# Apo_Board_2017_ATmega328_SMD.net
KiCad netlist of a schematic drawn in EAGLE
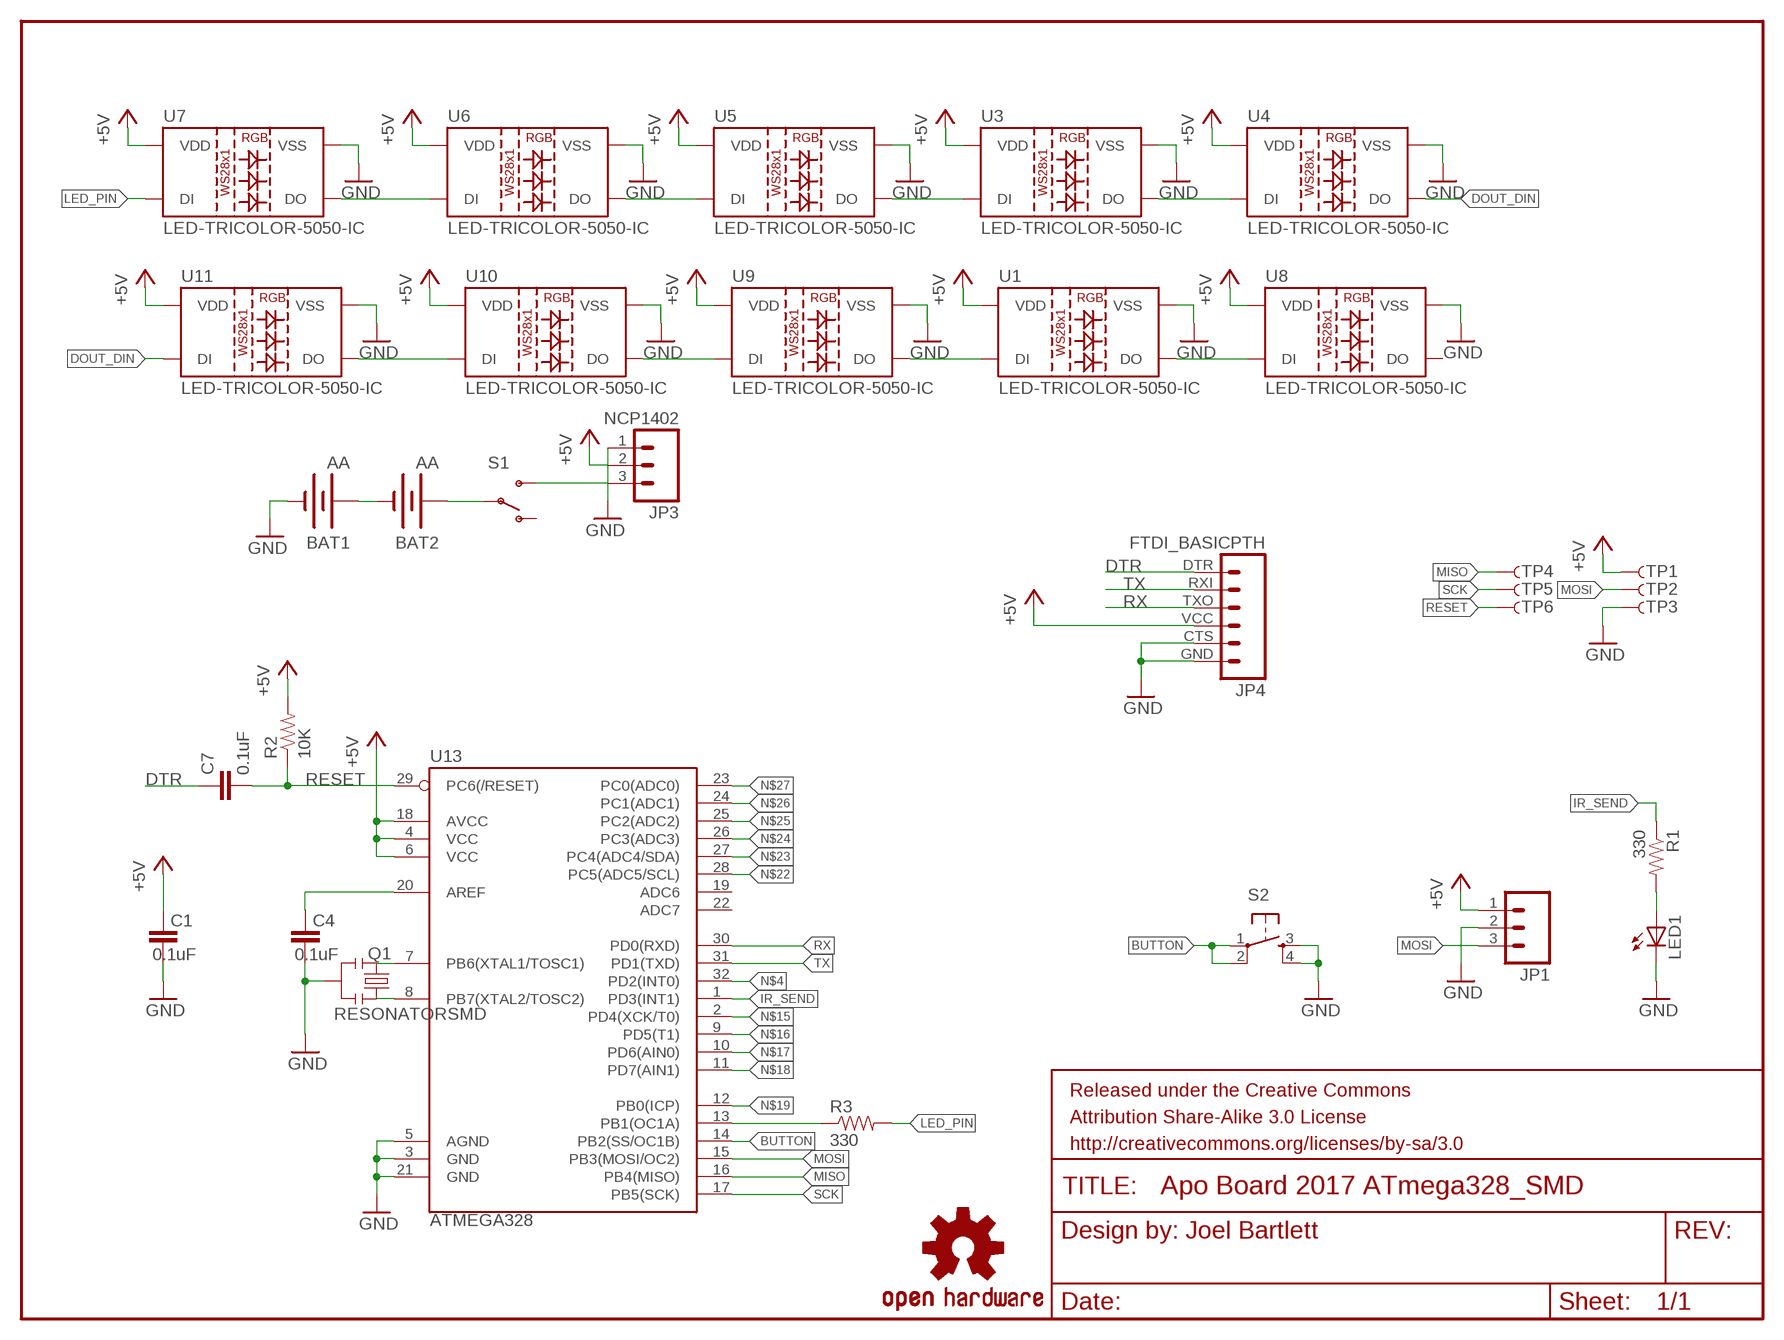
[diagram p0: schematic, sheet 1]

(export (version "E")
  (design (tool "Eeschema 10.0.6"))
  (components
    (comp (ref "BAT1")
      (value "AA")
      (footprint "eagle-import:BATTERY-AA-KIT")
      (libsource (lib "eagle-import") (part "BATTERYAA-KIT"))
    )
    (comp (ref "BAT2")
      (value "AA")
      (footprint "eagle-import:BATTERY-AA-KIT")
      (libsource (lib "eagle-import") (part "BATTERYAA-KIT"))
    )
    (comp (ref "C1")
      (value "0.1uF")
      (footprint "eagle-import:0402-CAP")
      (libsource (lib "eagle-import") (part "CAP0402-CAP"))
    )
    (comp (ref "C4")
      (value "0.1uF")
      (footprint "eagle-import:0402-CAP")
      (libsource (lib "eagle-import") (part "CAP0402-CAP"))
    )
    (comp (ref "C7")
      (value "0.1uF")
      (footprint "eagle-import:0402-CAP")
      (libsource (lib "eagle-import") (part "CAP0402-CAP"))
    )
    (comp (ref "FRAME1")
      (value "FRAME-LETTER")
      (footprint "eagle-import:CREATIVE_COMMONS")
      (libsource (lib "eagle-import") (part "FRAME-LETTER"))
    )
    (comp (ref "JP1")
      (value "M03IR_RECEIVER")
      (footprint "eagle-import:1X03_IR_RECEIVER")
      (libsource (lib "eagle-import") (part "M03IR_RECEIVER"))
    )
    (comp (ref "JP3")
      (value "NCP1402")
      (footprint "eagle-import:1X03_BOOST")
      (libsource (lib "eagle-import") (part "M03BOOST"))
    )
    (comp (ref "JP4")
      (value "FTDI_BASICPTH")
      (footprint "eagle-import:FTDI_BASIC")
      (libsource (lib "eagle-import") (part "FTDI_BASICPTH"))
    )
    (comp (ref "LED1")
      (value "LED5MM")
      (footprint "eagle-import:LED5MM")
      (libsource (lib "eagle-import") (part "LED5MM"))
    )
    (comp (ref "LOGO1")
      (value "OSHW-LOGOS")
      (footprint "eagle-import:OSHW-LOGO-S")
      (libsource (lib "eagle-import") (part "OSHW-LOGOS"))
    )
    (comp (ref "Q1")
      (value "RESONATORSMD")
      (footprint "eagle-import:RESONATOR-SMD")
      (libsource (lib "eagle-import") (part "RESONATORSMD"))
    )
    (comp (ref "R1")
      (value "330")
      (footprint "eagle-import:AXIAL-0.4")
      (libsource (lib "eagle-import") (part "SparkFun-Resistors_RESISTORPTH-1/4W"))
    )
    (comp (ref "R2")
      (value "10K")
      (footprint "eagle-import:0402-RES")
      (libsource (lib "eagle-import") (part "RESISTOR0402-RES"))
    )
    (comp (ref "R3")
      (value "330")
      (footprint "eagle-import:AXIAL-0.4")
      (libsource (lib "eagle-import") (part "SparkFun-Resistors_RESISTORPTH-1/4W"))
    )
    (comp (ref "S1")
      (value "SWITCH-SPSTKIT")
      (footprint "eagle-import:SWITCH-SPDT_KIT")
      (libsource (lib "eagle-import") (part "SWITCH-SPSTKIT"))
    )
    (comp (ref "S2")
      (value "TAC_SWITCHPTH")
      (footprint "eagle-import:TACTILE-PTH")
      (libsource (lib "eagle-import") (part "TAC_SWITCHPTH"))
    )
    (comp (ref "TP1")
      (value "TP-3x5")
      (footprint "eagle-import:PAD.03X.05")
      (libsource (lib "eagle-import") (part "TEST-POINT3X5"))
    )
    (comp (ref "TP2")
      (value "TP-3x5")
      (footprint "eagle-import:PAD.03X.05")
      (libsource (lib "eagle-import") (part "TEST-POINT3X5"))
    )
    (comp (ref "TP3")
      (value "TP-3x5")
      (footprint "eagle-import:PAD.03X.05")
      (libsource (lib "eagle-import") (part "TEST-POINT3X5"))
    )
    (comp (ref "TP4")
      (value "TP-3x5")
      (footprint "eagle-import:PAD.03X.05")
      (libsource (lib "eagle-import") (part "TEST-POINT3X5"))
    )
    (comp (ref "TP5")
      (value "TP-3x5")
      (footprint "eagle-import:PAD.03X.05")
      (libsource (lib "eagle-import") (part "TEST-POINT3X5"))
    )
    (comp (ref "TP6")
      (value "TP-3x5")
      (footprint "eagle-import:PAD.03X.05")
      (libsource (lib "eagle-import") (part "TEST-POINT3X5"))
    )
    (comp (ref "U1")
      (value "LED-TRICOLOR-5050-IC")
      (footprint "eagle-import:LED-RGB-THRU")
      (libsource (lib "eagle-import") (part "LED-TRICOLOR-5050-IC"))
    )
    (comp (ref "U3")
      (value "LED-TRICOLOR-5050-IC")
      (footprint "eagle-import:LED-RGB-THRU")
      (libsource (lib "eagle-import") (part "LED-TRICOLOR-5050-IC"))
    )
    (comp (ref "U4")
      (value "LED-TRICOLOR-5050-IC")
      (footprint "eagle-import:LED-RGB-THRU")
      (libsource (lib "eagle-import") (part "LED-TRICOLOR-5050-IC"))
    )
    (comp (ref "U5")
      (value "LED-TRICOLOR-5050-IC")
      (footprint "eagle-import:LED-RGB-THRU")
      (libsource (lib "eagle-import") (part "LED-TRICOLOR-5050-IC"))
    )
    (comp (ref "U6")
      (value "LED-TRICOLOR-5050-IC")
      (footprint "eagle-import:LED-RGB-THRU")
      (libsource (lib "eagle-import") (part "LED-TRICOLOR-5050-IC"))
    )
    (comp (ref "U7")
      (value "LED-TRICOLOR-5050-IC")
      (footprint "eagle-import:LED-RGB-THRU")
      (libsource (lib "eagle-import") (part "LED-TRICOLOR-5050-IC"))
    )
    (comp (ref "U8")
      (value "LED-TRICOLOR-5050-IC")
      (footprint "eagle-import:LED-RGB-THRU")
      (libsource (lib "eagle-import") (part "LED-TRICOLOR-5050-IC"))
    )
    (comp (ref "U9")
      (value "LED-TRICOLOR-5050-IC")
      (footprint "eagle-import:LED-RGB-THRU")
      (libsource (lib "eagle-import") (part "LED-TRICOLOR-5050-IC"))
    )
    (comp (ref "U10")
      (value "LED-TRICOLOR-5050-IC")
      (footprint "eagle-import:LED-RGB-THRU")
      (libsource (lib "eagle-import") (part "LED-TRICOLOR-5050-IC"))
    )
    (comp (ref "U11")
      (value "LED-TRICOLOR-5050-IC")
      (footprint "eagle-import:LED-RGB-THRU")
      (libsource (lib "eagle-import") (part "LED-TRICOLOR-5050-IC"))
    )
    (comp (ref "U13")
      (value "ATMEGA328")
      (footprint "eagle-import:TQFP32-08")
      (libsource (lib "eagle-import") (part "ATMEGA168"))
    )
  )
  (nets
    (net (code "1") (name "+5V") (class "Default")
      (node (ref "C1") (pin "2") (pinfunction "2_2") (pintype "passive"))
      (node (ref "JP1") (pin "1") (pinfunction "1_1") (pintype "passive"))
      (node (ref "JP3") (pin "2") (pinfunction "2_2") (pintype "passive"))
      (node (ref "JP4") (pin "VCC") (pinfunction "4_VCC") (pintype "passive"))
      (node (ref "R2") (pin "2") (pinfunction "2_2") (pintype "passive"))
      (node (ref "TP1") (pin "P$1") (pinfunction "1_P$1") (pintype "bidirectional"))
      (node (ref "U1") (pin "2") (pinfunction "VDD_2") (pintype "bidirectional"))
      (node (ref "U10") (pin "2") (pinfunction "VDD_2") (pintype "bidirectional"))
      (node (ref "U11") (pin "2") (pinfunction "VDD_2") (pintype "bidirectional"))
      (node (ref "U13") (pin "18") (pinfunction "AVCC_18") (pintype "bidirectional"))
      (node (ref "U13") (pin "4") (pinfunction "VCC_4") (pintype "bidirectional"))
      (node (ref "U13") (pin "6") (pinfunction "VCC_6") (pintype "bidirectional"))
      (node (ref "U3") (pin "2") (pinfunction "VDD_2") (pintype "bidirectional"))
      (node (ref "U4") (pin "2") (pinfunction "VDD_2") (pintype "bidirectional"))
      (node (ref "U5") (pin "2") (pinfunction "VDD_2") (pintype "bidirectional"))
      (node (ref "U6") (pin "2") (pinfunction "VDD_2") (pintype "bidirectional"))
      (node (ref "U7") (pin "2") (pinfunction "VDD_2") (pintype "bidirectional"))
      (node (ref "U8") (pin "2") (pinfunction "VDD_2") (pintype "bidirectional"))
      (node (ref "U9") (pin "2") (pinfunction "VDD_2") (pintype "bidirectional"))
    )
    (net (code "2") (name "/DTR") (class "Default")
      (node (ref "C7") (pin "1") (pinfunction "1_1") (pintype "passive"))
      (node (ref "JP4") (pin "DTR") (pinfunction "1_DTR") (pintype "passive"))
    )
    (net (code "3") (name "BUTTON") (class "Default")
      (node (ref "S2") (pin "1") (pinfunction "1_1") (pintype "passive"))
      (node (ref "S2") (pin "2") (pinfunction "2_2") (pintype "passive"))
      (node (ref "U13") (pin "14") (pinfunction "PB2(SS/OC1B)_14") (pintype "bidirectional"))
    )
    (net (code "4") (name "DOUT_DIN") (class "Default")
      (node (ref "U11") (pin "1") (pinfunction "DI_1") (pintype "bidirectional"))
      (node (ref "U4") (pin "4") (pinfunction "DO_4") (pintype "bidirectional"))
    )
    (net (code "5") (name "GND") (class "Default")
      (node (ref "BAT1") (pin "GND@1") (pinfunction "-_GND@1") (pintype "power_in"))
      (node (ref "C1") (pin "1") (pinfunction "1_1") (pintype "passive"))
      (node (ref "C4") (pin "1") (pinfunction "1_1") (pintype "passive"))
      (node (ref "JP1") (pin "2") (pinfunction "2_2") (pintype "passive"))
      (node (ref "JP3") (pin "1") (pinfunction "1_1") (pintype "passive"))
      (node (ref "JP4") (pin "CTS") (pinfunction "5_CTS") (pintype "passive"))
      (node (ref "JP4") (pin "GND") (pinfunction "6_GND") (pintype "passive"))
      (node (ref "LED1") (pin "K") (pinfunction "C_K") (pintype "passive"))
      (node (ref "Q1") (pin "2") (pinfunction "2_2") (pintype "passive"))
      (node (ref "S2") (pin "3") (pinfunction "3_3") (pintype "passive"))
      (node (ref "S2") (pin "4") (pinfunction "4_4") (pintype "passive"))
      (node (ref "TP3") (pin "P$1") (pinfunction "1_P$1") (pintype "bidirectional"))
      (node (ref "U1") (pin "3") (pinfunction "VSS_3") (pintype "bidirectional"))
      (node (ref "U10") (pin "3") (pinfunction "VSS_3") (pintype "bidirectional"))
      (node (ref "U11") (pin "3") (pinfunction "VSS_3") (pintype "bidirectional"))
      (node (ref "U13") (pin "21") (pinfunction "GND_21") (pintype "bidirectional"))
      (node (ref "U13") (pin "3") (pinfunction "GND_3") (pintype "bidirectional"))
      (node (ref "U13") (pin "5") (pinfunction "AGND_5") (pintype "bidirectional"))
      (node (ref "U3") (pin "3") (pinfunction "VSS_3") (pintype "bidirectional"))
      (node (ref "U4") (pin "3") (pinfunction "VSS_3") (pintype "bidirectional"))
      (node (ref "U5") (pin "3") (pinfunction "VSS_3") (pintype "bidirectional"))
      (node (ref "U6") (pin "3") (pinfunction "VSS_3") (pintype "bidirectional"))
      (node (ref "U7") (pin "3") (pinfunction "VSS_3") (pintype "bidirectional"))
      (node (ref "U8") (pin "3") (pinfunction "VSS_3") (pintype "bidirectional"))
      (node (ref "U9") (pin "3") (pinfunction "VSS_3") (pintype "bidirectional"))
    )
    (net (code "6") (name "IR_SEND") (class "Default")
      (node (ref "R1") (pin "P$1") (pinfunction "1_P$1") (pintype "passive"))
      (node (ref "U13") (pin "1") (pinfunction "PD3(INT1)_1") (pintype "bidirectional"))
    )
    (net (code "7") (name "LED_PIN") (class "Default")
      (node (ref "R3") (pin "P$2") (pinfunction "2_P$2") (pintype "passive"))
      (node (ref "U7") (pin "1") (pinfunction "DI_1") (pintype "bidirectional"))
    )
    (net (code "8") (name "MISO") (class "Default")
      (node (ref "TP4") (pin "P$1") (pinfunction "1_P$1") (pintype "bidirectional"))
      (node (ref "U13") (pin "16") (pinfunction "PB4(MISO)_16") (pintype "bidirectional"))
    )
    (net (code "9") (name "MOSI") (class "Default")
      (node (ref "JP1") (pin "3") (pinfunction "3_3") (pintype "passive"))
      (node (ref "TP2") (pin "P$1") (pinfunction "1_P$1") (pintype "bidirectional"))
      (node (ref "U13") (pin "15") (pinfunction "PB3(MOSI/OC2)_15") (pintype "bidirectional"))
    )
    (net (code "10") (name "N$4") (class "Default")
      (node (ref "U13") (pin "32") (pinfunction "PD2(INT0)_32") (pintype "bidirectional"))
    )
    (net (code "11") (name "N$15") (class "Default")
      (node (ref "U13") (pin "2") (pinfunction "PD4(XCK/T0)_2") (pintype "bidirectional"))
    )
    (net (code "12") (name "N$16") (class "Default")
      (node (ref "U13") (pin "9") (pinfunction "PD5(T1)_9") (pintype "bidirectional"))
    )
    (net (code "13") (name "N$17") (class "Default")
      (node (ref "U13") (pin "10") (pinfunction "PD6(AIN0)_10") (pintype "bidirectional"))
    )
    (net (code "14") (name "N$18") (class "Default")
      (node (ref "U13") (pin "11") (pinfunction "PD7(AIN1)_11") (pintype "bidirectional"))
    )
    (net (code "15") (name "N$19") (class "Default")
      (node (ref "U13") (pin "12") (pinfunction "PB0(ICP)_12") (pintype "bidirectional"))
    )
    (net (code "16") (name "N$22") (class "Default")
      (node (ref "U13") (pin "28") (pinfunction "PC5(ADC5/SCL)_28") (pintype "bidirectional"))
    )
    (net (code "17") (name "N$23") (class "Default")
      (node (ref "U13") (pin "27") (pinfunction "PC4(ADC4/SDA)_27") (pintype "bidirectional"))
    )
    (net (code "18") (name "N$24") (class "Default")
      (node (ref "U13") (pin "26") (pinfunction "PC3(ADC3)_26") (pintype "bidirectional"))
    )
    (net (code "19") (name "N$25") (class "Default")
      (node (ref "U13") (pin "25") (pinfunction "PC2(ADC2)_25") (pintype "bidirectional"))
    )
    (net (code "20") (name "N$26") (class "Default")
      (node (ref "U13") (pin "24") (pinfunction "PC1(ADC1)_24") (pintype "bidirectional"))
    )
    (net (code "21") (name "N$27") (class "Default")
      (node (ref "U13") (pin "23") (pinfunction "PC0(ADC0)_23") (pintype "bidirectional"))
    )
    (net (code "22") (name "Net-(BAT1-+)") (class "Default")
      (node (ref "BAT1") (pin "PWR@1") (pinfunction "+_PWR@1") (pintype "power_in"))
      (node (ref "BAT2") (pin "GND@1") (pinfunction "-_GND@1") (pintype "power_in"))
    )
    (net (code "23") (name "Net-(BAT2-+)") (class "Default")
      (node (ref "BAT2") (pin "PWR@1") (pinfunction "+_PWR@1") (pintype "power_in"))
      (node (ref "S1") (pin "2") (pinfunction "P_2") (pintype "passive"))
    )
    (net (code "24") (name "Net-(R1-2)") (class "Default")
      (node (ref "LED1") (pin "A") (pinfunction "A_A") (pintype "passive"))
      (node (ref "R1") (pin "P$2") (pinfunction "2_P$2") (pintype "passive"))
    )
    (net (code "25") (name "Net-(R3-1)") (class "Default")
      (node (ref "R3") (pin "P$1") (pinfunction "1_P$1") (pintype "passive"))
      (node (ref "U13") (pin "13") (pinfunction "PB1(OC1A)_13") (pintype "bidirectional"))
    )
    (net (code "26") (name "Net-(S1-S)") (class "Default")
      (node (ref "JP3") (pin "3") (pinfunction "3_3") (pintype "passive"))
      (node (ref "S1") (pin "3") (pinfunction "S_3") (pintype "passive"))
    )
    (net (code "27") (name "Net-(U1-DI)") (class "Default")
      (node (ref "U1") (pin "1") (pinfunction "DI_1") (pintype "bidirectional"))
      (node (ref "U9") (pin "4") (pinfunction "DO_4") (pintype "bidirectional"))
    )
    (net (code "28") (name "Net-(U1-DO)") (class "Default")
      (node (ref "U1") (pin "4") (pinfunction "DO_4") (pintype "bidirectional"))
      (node (ref "U8") (pin "1") (pinfunction "DI_1") (pintype "bidirectional"))
    )
    (net (code "29") (name "Net-(U3-DI)") (class "Default")
      (node (ref "U3") (pin "1") (pinfunction "DI_1") (pintype "bidirectional"))
      (node (ref "U5") (pin "4") (pinfunction "DO_4") (pintype "bidirectional"))
    )
    (net (code "30") (name "Net-(U3-DO)") (class "Default")
      (node (ref "U3") (pin "4") (pinfunction "DO_4") (pintype "bidirectional"))
      (node (ref "U4") (pin "1") (pinfunction "DI_1") (pintype "bidirectional"))
    )
    (net (code "31") (name "Net-(U5-DI)") (class "Default")
      (node (ref "U5") (pin "1") (pinfunction "DI_1") (pintype "bidirectional"))
      (node (ref "U6") (pin "4") (pinfunction "DO_4") (pintype "bidirectional"))
    )
    (net (code "32") (name "Net-(U6-DI)") (class "Default")
      (node (ref "U6") (pin "1") (pinfunction "DI_1") (pintype "bidirectional"))
      (node (ref "U7") (pin "4") (pinfunction "DO_4") (pintype "bidirectional"))
    )
    (net (code "33") (name "Net-(U10-DI)") (class "Default")
      (node (ref "U10") (pin "1") (pinfunction "DI_1") (pintype "bidirectional"))
      (node (ref "U11") (pin "4") (pinfunction "DO_4") (pintype "bidirectional"))
    )
    (net (code "34") (name "Net-(U10-DO)") (class "Default")
      (node (ref "U10") (pin "4") (pinfunction "DO_4") (pintype "bidirectional"))
      (node (ref "U9") (pin "1") (pinfunction "DI_1") (pintype "bidirectional"))
    )
    (net (code "35") (name "Net-(U13-AREF)") (class "Default")
      (node (ref "C4") (pin "2") (pinfunction "2_2") (pintype "passive"))
      (node (ref "U13") (pin "20") (pinfunction "AREF_20") (pintype "bidirectional"))
    )
    (net (code "36") (name "Net-(U13-PB6(XTAL1{slash}TOSC1))") (class "Default")
      (node (ref "Q1") (pin "3") (pinfunction "3_3") (pintype "passive"))
      (node (ref "U13") (pin "7") (pinfunction "PB6(XTAL1/TOSC1)_7") (pintype "bidirectional"))
    )
    (net (code "37") (name "Net-(U13-PB7(XTAL2{slash}TOSC2))") (class "Default")
      (node (ref "Q1") (pin "1") (pinfunction "1_1") (pintype "passive"))
      (node (ref "U13") (pin "8") (pinfunction "PB7(XTAL2/TOSC2)_8") (pintype "bidirectional"))
    )
    (net (code "38") (name "RESET") (class "Default")
      (node (ref "C7") (pin "2") (pinfunction "2_2") (pintype "passive"))
      (node (ref "R2") (pin "1") (pinfunction "1_1") (pintype "passive"))
      (node (ref "TP6") (pin "P$1") (pinfunction "1_P$1") (pintype "bidirectional"))
      (node (ref "U13") (pin "29") (pinfunction "PC6(/RESET)_29") (pintype "bidirectional"))
    )
    (net (code "39") (name "RX") (class "Default")
      (node (ref "JP4") (pin "TXO") (pinfunction "3_TXO") (pintype "passive"))
      (node (ref "U13") (pin "30") (pinfunction "PD0(RXD)_30") (pintype "bidirectional"))
    )
    (net (code "40") (name "SCK") (class "Default")
      (node (ref "TP5") (pin "P$1") (pinfunction "1_P$1") (pintype "bidirectional"))
      (node (ref "U13") (pin "17") (pinfunction "PB5(SCK)_17") (pintype "bidirectional"))
    )
    (net (code "41") (name "TX") (class "Default")
      (node (ref "JP4") (pin "RXI") (pinfunction "2_RXI") (pintype "passive"))
      (node (ref "U13") (pin "31") (pinfunction "PD1(TXD)_31") (pintype "bidirectional"))
    )
    (net (code "42") (name "unconnected-(S1-O-Pad1)") (class "Default")
      (node (ref "S1") (pin "1") (pinfunction "O_1") (pintype "passive"))
    )
    (net (code "43") (name "unconnected-(U8-DO-Pad4)") (class "Default")
      (node (ref "U8") (pin "4") (pinfunction "DO_4") (pintype "bidirectional"))
    )
    (net (code "44") (name "unconnected-(U13-ADC6-Pad19)") (class "Default")
      (node (ref "U13") (pin "19") (pinfunction "ADC6_19") (pintype "bidirectional"))
    )
    (net (code "45") (name "unconnected-(U13-ADC7-Pad22)") (class "Default")
      (node (ref "U13") (pin "22") (pinfunction "ADC7_22") (pintype "bidirectional"))
    )
  )
)
